# ASBB_BMP388.net
KiCad netlist of a schematic drawn in Altium Designer
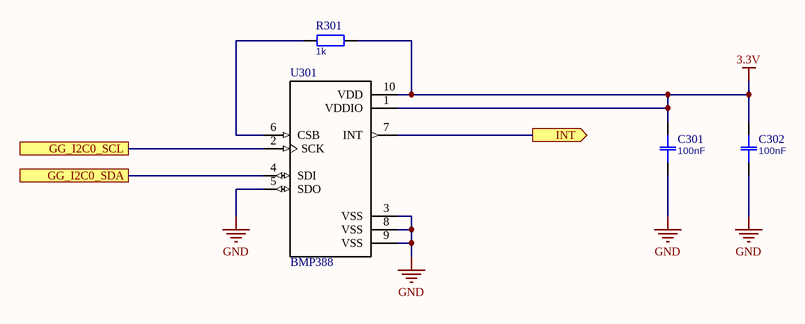
[diagram p0: ASBB_BMP388.SchDoc]

(export (version "E")
  (design (tool "Eeschema 10.0.6"))
  (components
    (comp (ref "C301")
      (value "100nF")
      (footprint "0603")
      (description "Capacitor")
      (fields (field (name "PARTNUMBER") "?"))
      (libsource (lib "FZI") (part "Capacitor"))
    )
    (comp (ref "C302")
      (value "100nF")
      (footprint "0603")
      (description "Capacitor")
      (fields (field (name "PARTNUMBER") "?"))
      (libsource (lib "FZI") (part "Capacitor"))
    )
    (comp (ref "R301")
      (value "1k")
      (footprint "0603")
      (description "Resistor")
      (fields (field (name "PARTNUMBER") "?"))
      (libsource (lib "FZI") (part "Resistor"))
    )
    (comp (ref "U301")
      (value "BMP388")
      (footprint "BMP388:PQFN50P200X200X80-10N")
      (description "P-Sensor SPI I2C 1, 25 Bar SMD")
      (fields (field (name "MF") "Bosch Sensortec"))
      (libsource (lib "BMP388") (part "BMP388"))
    )
  )
  (nets
    (net (code "1") (name "/GG_I2C0_SCL") (class "Default")
      (node (ref "U301") (pin "2") (pinfunction "SCK_2") (pintype "input"))
    )
    (net (code "2") (name "/GG_I2C0_SDA") (class "Default")
      (node (ref "U301") (pin "4") (pinfunction "SDI_4") (pintype "bidirectional"))
    )
    (net (code "3") (name "/INT") (class "Default")
      (node (ref "U301") (pin "7") (pinfunction "INT_7") (pintype "output"))
    )
    (net (code "4") (name "3.3V") (class "Default")
      (node (ref "C301") (pin "2") (pinfunction "2_2") (pintype "passive"))
      (node (ref "C302") (pin "2") (pinfunction "2_2") (pintype "passive"))
      (node (ref "R301") (pin "2") (pinfunction "2_2") (pintype "passive"))
      (node (ref "U301") (pin "1") (pinfunction "VDDIO_1") (pintype "power_in"))
      (node (ref "U301") (pin "10") (pinfunction "VDD_10") (pintype "power_in"))
    )
    (net (code "5") (name "GND") (class "Default")
      (node (ref "C301") (pin "1") (pinfunction "1_1") (pintype "passive"))
      (node (ref "C302") (pin "1") (pinfunction "1_1") (pintype "passive"))
      (node (ref "U301") (pin "3") (pinfunction "VSS_3") (pintype "power_in"))
      (node (ref "U301") (pin "5") (pinfunction "SDO_5") (pintype "bidirectional"))
      (node (ref "U301") (pin "8") (pinfunction "VSS_8") (pintype "power_in"))
      (node (ref "U301") (pin "9") (pinfunction "VSS_9") (pintype "power_in"))
    )
    (net (code "6") (name "Net-(U301-CSB)") (class "Default")
      (node (ref "R301") (pin "1") (pinfunction "1_1") (pintype "passive"))
      (node (ref "U301") (pin "6") (pinfunction "CSB_6") (pintype "input"))
    )
  )
)
